# dummy_battery.net
KiCad netlist of a schematic drawn in EAGLE
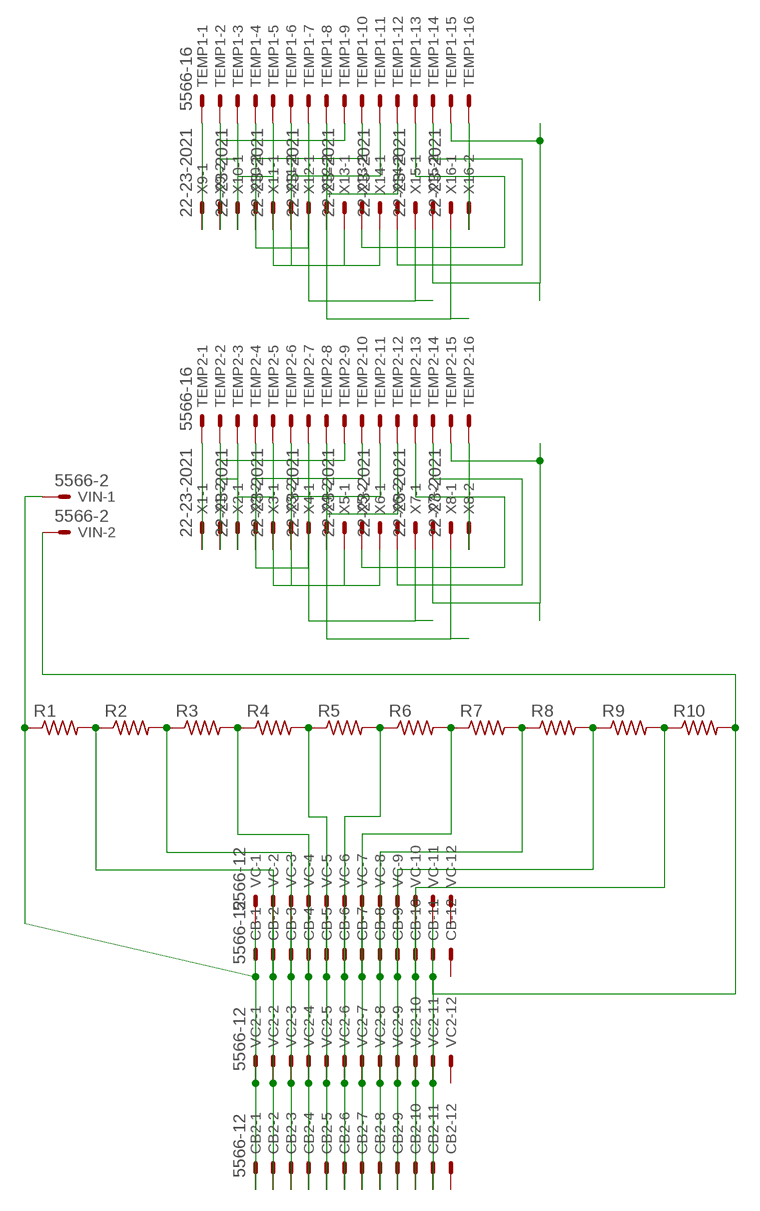
[diagram p0: schematic, sheet 1]

(export (version "E")
  (design (tool "Eeschema 10.0.6"))
  (components
    (comp (ref "CB")
      (value "5566-12")
      (footprint "eagle-import:5566-12")
      (fields (field (name "MF") "MOLEX"))
      (libsource (lib "eagle-import") (part "5566-12"))
    )
    (comp (ref "CB2")
      (value "5566-12")
      (footprint "eagle-import:5566-12")
      (fields (field (name "MF") "MOLEX"))
      (libsource (lib "eagle-import") (part "5566-12"))
    )
    (comp (ref "R1")
      (value "R-US_R0805")
      (footprint "eagle-import:R0805")
      (libsource (lib "eagle-import") (part "R-US_R0805"))
    )
    (comp (ref "R2")
      (value "R-US_R0805")
      (footprint "eagle-import:R0805")
      (libsource (lib "eagle-import") (part "R-US_R0805"))
    )
    (comp (ref "R3")
      (value "R-US_R0805")
      (footprint "eagle-import:R0805")
      (libsource (lib "eagle-import") (part "R-US_R0805"))
    )
    (comp (ref "R4")
      (value "R-US_R0805")
      (footprint "eagle-import:R0805")
      (libsource (lib "eagle-import") (part "R-US_R0805"))
    )
    (comp (ref "R5")
      (value "R-US_R0805")
      (footprint "eagle-import:R0805")
      (libsource (lib "eagle-import") (part "R-US_R0805"))
    )
    (comp (ref "R6")
      (value "R-US_R0805")
      (footprint "eagle-import:R0805")
      (libsource (lib "eagle-import") (part "R-US_R0805"))
    )
    (comp (ref "R7")
      (value "R-US_R0805")
      (footprint "eagle-import:R0805")
      (libsource (lib "eagle-import") (part "R-US_R0805"))
    )
    (comp (ref "R8")
      (value "R-US_R0805")
      (footprint "eagle-import:R0805")
      (libsource (lib "eagle-import") (part "R-US_R0805"))
    )
    (comp (ref "R9")
      (value "R-US_R0805")
      (footprint "eagle-import:R0805")
      (libsource (lib "eagle-import") (part "R-US_R0805"))
    )
    (comp (ref "R10")
      (value "R-US_R0805")
      (footprint "eagle-import:R0805")
      (libsource (lib "eagle-import") (part "R-US_R0805"))
    )
    (comp (ref "TEMP1")
      (value "5566-16")
      (footprint "eagle-import:5566-16")
      (fields (field (name "MF") "MOLEX"))
      (libsource (lib "eagle-import") (part "5566-16"))
    )
    (comp (ref "TEMP2")
      (value "5566-16")
      (footprint "eagle-import:5566-16")
      (fields (field (name "MF") "MOLEX"))
      (libsource (lib "eagle-import") (part "5566-16"))
    )
    (comp (ref "VC")
      (value "5566-12")
      (footprint "eagle-import:5566-12")
      (fields (field (name "MF") "MOLEX"))
      (libsource (lib "eagle-import") (part "5566-12"))
    )
    (comp (ref "VC2")
      (value "5566-12")
      (footprint "eagle-import:5566-12")
      (fields (field (name "MF") "MOLEX"))
      (libsource (lib "eagle-import") (part "5566-12"))
    )
    (comp (ref "VIN")
      (value "5566-2")
      (footprint "eagle-import:5566-2")
      (fields (field (name "MF") "MOLEX"))
      (libsource (lib "eagle-import") (part "5566-2"))
    )
    (comp (ref "X1")
      (value "22-23-2021")
      (footprint "eagle-import:22-23-2021")
      (fields (field (name "MF") "MOLEX"))
      (libsource (lib "eagle-import") (part "22-23-2021"))
    )
    (comp (ref "X2")
      (value "22-23-2021")
      (footprint "eagle-import:22-23-2021")
      (fields (field (name "MF") "MOLEX"))
      (libsource (lib "eagle-import") (part "22-23-2021"))
    )
    (comp (ref "X3")
      (value "22-23-2021")
      (footprint "eagle-import:22-23-2021")
      (fields (field (name "MF") "MOLEX"))
      (libsource (lib "eagle-import") (part "22-23-2021"))
    )
    (comp (ref "X4")
      (value "22-23-2021")
      (footprint "eagle-import:22-23-2021")
      (fields (field (name "MF") "MOLEX"))
      (libsource (lib "eagle-import") (part "22-23-2021"))
    )
    (comp (ref "X5")
      (value "22-23-2021")
      (footprint "eagle-import:22-23-2021")
      (fields (field (name "MF") "MOLEX"))
      (libsource (lib "eagle-import") (part "22-23-2021"))
    )
    (comp (ref "X6")
      (value "22-23-2021")
      (footprint "eagle-import:22-23-2021")
      (fields (field (name "MF") "MOLEX"))
      (libsource (lib "eagle-import") (part "22-23-2021"))
    )
    (comp (ref "X7")
      (value "22-23-2021")
      (footprint "eagle-import:22-23-2021")
      (fields (field (name "MF") "MOLEX"))
      (libsource (lib "eagle-import") (part "22-23-2021"))
    )
    (comp (ref "X8")
      (value "22-23-2021")
      (footprint "eagle-import:22-23-2021")
      (fields (field (name "MF") "MOLEX"))
      (libsource (lib "eagle-import") (part "22-23-2021"))
    )
    (comp (ref "X9")
      (value "22-23-2021")
      (footprint "eagle-import:22-23-2021")
      (fields (field (name "MF") "MOLEX"))
      (libsource (lib "eagle-import") (part "22-23-2021"))
    )
    (comp (ref "X10")
      (value "22-23-2021")
      (footprint "eagle-import:22-23-2021")
      (fields (field (name "MF") "MOLEX"))
      (libsource (lib "eagle-import") (part "22-23-2021"))
    )
    (comp (ref "X11")
      (value "22-23-2021")
      (footprint "eagle-import:22-23-2021")
      (fields (field (name "MF") "MOLEX"))
      (libsource (lib "eagle-import") (part "22-23-2021"))
    )
    (comp (ref "X12")
      (value "22-23-2021")
      (footprint "eagle-import:22-23-2021")
      (fields (field (name "MF") "MOLEX"))
      (libsource (lib "eagle-import") (part "22-23-2021"))
    )
    (comp (ref "X13")
      (value "22-23-2021")
      (footprint "eagle-import:22-23-2021")
      (fields (field (name "MF") "MOLEX"))
      (libsource (lib "eagle-import") (part "22-23-2021"))
    )
    (comp (ref "X14")
      (value "22-23-2021")
      (footprint "eagle-import:22-23-2021")
      (fields (field (name "MF") "MOLEX"))
      (libsource (lib "eagle-import") (part "22-23-2021"))
    )
    (comp (ref "X15")
      (value "22-23-2021")
      (footprint "eagle-import:22-23-2021")
      (fields (field (name "MF") "MOLEX"))
      (libsource (lib "eagle-import") (part "22-23-2021"))
    )
    (comp (ref "X16")
      (value "22-23-2021")
      (footprint "eagle-import:22-23-2021")
      (fields (field (name "MF") "MOLEX"))
      (libsource (lib "eagle-import") (part "22-23-2021"))
    )
  )
  (nets
    (net (code "1") (name "Net-(CB2A-S)") (class "Default")
      (node (ref "CB") (pin "1") (pinfunction "S_1") (pintype "passive"))
      (node (ref "CB2") (pin "1") (pinfunction "S_1") (pintype "passive"))
      (node (ref "R1") (pin "1") (pinfunction "1_1") (pintype "passive"))
      (node (ref "VC") (pin "1") (pinfunction "S_1") (pintype "passive"))
      (node (ref "VC2") (pin "1") (pinfunction "S_1") (pintype "passive"))
      (node (ref "VIN") (pin "1") (pinfunction "S_1") (pintype "passive"))
    )
    (net (code "2") (name "Net-(CB2B-S)") (class "Default")
      (node (ref "CB") (pin "10") (pinfunction "S_10") (pintype "passive"))
      (node (ref "CB2") (pin "10") (pinfunction "S_10") (pintype "passive"))
      (node (ref "R10") (pin "1") (pinfunction "1_1") (pintype "passive"))
      (node (ref "R9") (pin "2") (pinfunction "2_2") (pintype "passive"))
      (node (ref "VC") (pin "10") (pinfunction "S_10") (pintype "passive"))
      (node (ref "VC2") (pin "10") (pinfunction "S_10") (pintype "passive"))
    )
    (net (code "3") (name "Net-(CB2C-S)") (class "Default")
      (node (ref "CB") (pin "11") (pinfunction "S_11") (pintype "passive"))
      (node (ref "CB2") (pin "11") (pinfunction "S_11") (pintype "passive"))
      (node (ref "R10") (pin "2") (pinfunction "2_2") (pintype "passive"))
      (node (ref "VC") (pin "11") (pinfunction "S_11") (pintype "passive"))
      (node (ref "VC2") (pin "11") (pinfunction "S_11") (pintype "passive"))
      (node (ref "VIN") (pin "2") (pinfunction "S_2") (pintype "passive"))
    )
    (net (code "4") (name "Net-(CB2E-S)") (class "Default")
      (node (ref "CB") (pin "2") (pinfunction "S_2") (pintype "passive"))
      (node (ref "CB2") (pin "2") (pinfunction "S_2") (pintype "passive"))
      (node (ref "R1") (pin "2") (pinfunction "2_2") (pintype "passive"))
      (node (ref "R2") (pin "1") (pinfunction "1_1") (pintype "passive"))
      (node (ref "VC") (pin "2") (pinfunction "S_2") (pintype "passive"))
      (node (ref "VC2") (pin "2") (pinfunction "S_2") (pintype "passive"))
    )
    (net (code "5") (name "Net-(CB2F-S)") (class "Default")
      (node (ref "CB") (pin "3") (pinfunction "S_3") (pintype "passive"))
      (node (ref "CB2") (pin "3") (pinfunction "S_3") (pintype "passive"))
      (node (ref "R2") (pin "2") (pinfunction "2_2") (pintype "passive"))
      (node (ref "R3") (pin "1") (pinfunction "1_1") (pintype "passive"))
      (node (ref "VC") (pin "3") (pinfunction "S_3") (pintype "passive"))
      (node (ref "VC2") (pin "3") (pinfunction "S_3") (pintype "passive"))
    )
    (net (code "6") (name "Net-(CB2G-S)") (class "Default")
      (node (ref "CB") (pin "4") (pinfunction "S_4") (pintype "passive"))
      (node (ref "CB2") (pin "4") (pinfunction "S_4") (pintype "passive"))
      (node (ref "R3") (pin "2") (pinfunction "2_2") (pintype "passive"))
      (node (ref "R4") (pin "1") (pinfunction "1_1") (pintype "passive"))
      (node (ref "VC") (pin "4") (pinfunction "S_4") (pintype "passive"))
      (node (ref "VC2") (pin "4") (pinfunction "S_4") (pintype "passive"))
    )
    (net (code "7") (name "Net-(CB2H-S)") (class "Default")
      (node (ref "CB") (pin "5") (pinfunction "S_5") (pintype "passive"))
      (node (ref "CB2") (pin "5") (pinfunction "S_5") (pintype "passive"))
      (node (ref "R4") (pin "2") (pinfunction "2_2") (pintype "passive"))
      (node (ref "R5") (pin "1") (pinfunction "1_1") (pintype "passive"))
      (node (ref "VC") (pin "5") (pinfunction "S_5") (pintype "passive"))
      (node (ref "VC2") (pin "5") (pinfunction "S_5") (pintype "passive"))
    )
    (net (code "8") (name "Net-(CB2I-S)") (class "Default")
      (node (ref "CB") (pin "6") (pinfunction "S_6") (pintype "passive"))
      (node (ref "CB2") (pin "6") (pinfunction "S_6") (pintype "passive"))
      (node (ref "R5") (pin "2") (pinfunction "2_2") (pintype "passive"))
      (node (ref "R6") (pin "1") (pinfunction "1_1") (pintype "passive"))
      (node (ref "VC") (pin "6") (pinfunction "S_6") (pintype "passive"))
      (node (ref "VC2") (pin "6") (pinfunction "S_6") (pintype "passive"))
    )
    (net (code "9") (name "Net-(CB2J-S)") (class "Default")
      (node (ref "CB") (pin "7") (pinfunction "S_7") (pintype "passive"))
      (node (ref "CB2") (pin "7") (pinfunction "S_7") (pintype "passive"))
      (node (ref "R6") (pin "2") (pinfunction "2_2") (pintype "passive"))
      (node (ref "R7") (pin "1") (pinfunction "1_1") (pintype "passive"))
      (node (ref "VC") (pin "7") (pinfunction "S_7") (pintype "passive"))
      (node (ref "VC2") (pin "7") (pinfunction "S_7") (pintype "passive"))
    )
    (net (code "10") (name "Net-(CB2K-S)") (class "Default")
      (node (ref "CB") (pin "8") (pinfunction "S_8") (pintype "passive"))
      (node (ref "CB2") (pin "8") (pinfunction "S_8") (pintype "passive"))
      (node (ref "R7") (pin "2") (pinfunction "2_2") (pintype "passive"))
      (node (ref "R8") (pin "1") (pinfunction "1_1") (pintype "passive"))
      (node (ref "VC") (pin "8") (pinfunction "S_8") (pintype "passive"))
      (node (ref "VC2") (pin "8") (pinfunction "S_8") (pintype "passive"))
    )
    (net (code "11") (name "Net-(CB2L-S)") (class "Default")
      (node (ref "CB") (pin "9") (pinfunction "S_9") (pintype "passive"))
      (node (ref "CB2") (pin "9") (pinfunction "S_9") (pintype "passive"))
      (node (ref "R8") (pin "2") (pinfunction "2_2") (pintype "passive"))
      (node (ref "R9") (pin "1") (pinfunction "1_1") (pintype "passive"))
      (node (ref "VC") (pin "9") (pinfunction "S_9") (pintype "passive"))
      (node (ref "VC2") (pin "9") (pinfunction "S_9") (pintype "passive"))
    )
    (net (code "12") (name "Net-(TEMP1A-S)") (class "Default")
      (node (ref "TEMP1") (pin "1") (pinfunction "S_1") (pintype "passive"))
      (node (ref "X9") (pin "1") (pinfunction "S_1") (pintype "passive"))
    )
    (net (code "13") (name "Net-(TEMP1B-S)") (class "Default")
      (node (ref "TEMP1") (pin "10") (pinfunction "S_10") (pintype "passive"))
      (node (ref "X10") (pin "2") (pinfunction "S_2") (pintype "passive"))
    )
    (net (code "14") (name "Net-(TEMP1C-S)") (class "Default")
      (node (ref "TEMP1") (pin "11") (pinfunction "S_11") (pintype "passive"))
      (node (ref "X11") (pin "2") (pinfunction "S_2") (pintype "passive"))
    )
    (net (code "15") (name "Net-(TEMP1D-S)") (class "Default")
      (node (ref "TEMP1") (pin "12") (pinfunction "S_12") (pintype "passive"))
      (node (ref "X12") (pin "2") (pinfunction "S_2") (pintype "passive"))
    )
    (net (code "16") (name "Net-(TEMP1E-S)") (class "Default")
      (node (ref "TEMP1") (pin "13") (pinfunction "S_13") (pintype "passive"))
      (node (ref "X13") (pin "2") (pinfunction "S_2") (pintype "passive"))
    )
    (net (code "17") (name "Net-(TEMP1F-S)") (class "Default")
      (node (ref "TEMP1") (pin "14") (pinfunction "S_14") (pintype "passive"))
      (node (ref "X14") (pin "2") (pinfunction "S_2") (pintype "passive"))
    )
    (net (code "18") (name "Net-(TEMP1G-S)") (class "Default")
      (node (ref "TEMP1") (pin "15") (pinfunction "S_15") (pintype "passive"))
      (node (ref "X15") (pin "2") (pinfunction "S_2") (pintype "passive"))
    )
    (net (code "19") (name "Net-(TEMP1H-S)") (class "Default")
      (node (ref "TEMP1") (pin "16") (pinfunction "S_16") (pintype "passive"))
      (node (ref "X16") (pin "2") (pinfunction "S_2") (pintype "passive"))
    )
    (net (code "20") (name "Net-(TEMP1I-S)") (class "Default")
      (node (ref "TEMP1") (pin "2") (pinfunction "S_2") (pintype "passive"))
      (node (ref "X10") (pin "1") (pinfunction "S_1") (pintype "passive"))
    )
    (net (code "21") (name "Net-(TEMP1J-S)") (class "Default")
      (node (ref "TEMP1") (pin "3") (pinfunction "S_3") (pintype "passive"))
      (node (ref "X11") (pin "1") (pinfunction "S_1") (pintype "passive"))
    )
    (net (code "22") (name "Net-(TEMP1K-S)") (class "Default")
      (node (ref "TEMP1") (pin "4") (pinfunction "S_4") (pintype "passive"))
      (node (ref "X12") (pin "1") (pinfunction "S_1") (pintype "passive"))
    )
    (net (code "23") (name "Net-(TEMP1L-S)") (class "Default")
      (node (ref "TEMP1") (pin "5") (pinfunction "S_5") (pintype "passive"))
      (node (ref "X13") (pin "1") (pinfunction "S_1") (pintype "passive"))
    )
    (net (code "24") (name "Net-(TEMP1M-S)") (class "Default")
      (node (ref "TEMP1") (pin "6") (pinfunction "S_6") (pintype "passive"))
      (node (ref "X14") (pin "1") (pinfunction "S_1") (pintype "passive"))
    )
    (net (code "25") (name "Net-(TEMP1N-S)") (class "Default")
      (node (ref "TEMP1") (pin "7") (pinfunction "S_7") (pintype "passive"))
      (node (ref "X15") (pin "1") (pinfunction "S_1") (pintype "passive"))
    )
    (net (code "26") (name "Net-(TEMP1O-S)") (class "Default")
      (node (ref "TEMP1") (pin "8") (pinfunction "S_8") (pintype "passive"))
      (node (ref "X16") (pin "1") (pinfunction "S_1") (pintype "passive"))
    )
    (net (code "27") (name "Net-(TEMP1P-S)") (class "Default")
      (node (ref "TEMP1") (pin "9") (pinfunction "S_9") (pintype "passive"))
      (node (ref "X9") (pin "2") (pinfunction "S_2") (pintype "passive"))
    )
    (net (code "28") (name "Net-(TEMP2A-S)") (class "Default")
      (node (ref "TEMP2") (pin "1") (pinfunction "S_1") (pintype "passive"))
      (node (ref "X1") (pin "1") (pinfunction "S_1") (pintype "passive"))
    )
    (net (code "29") (name "Net-(TEMP2B-S)") (class "Default")
      (node (ref "TEMP2") (pin "10") (pinfunction "S_10") (pintype "passive"))
      (node (ref "X2") (pin "2") (pinfunction "S_2") (pintype "passive"))
    )
    (net (code "30") (name "Net-(TEMP2C-S)") (class "Default")
      (node (ref "TEMP2") (pin "11") (pinfunction "S_11") (pintype "passive"))
      (node (ref "X3") (pin "2") (pinfunction "S_2") (pintype "passive"))
    )
    (net (code "31") (name "Net-(TEMP2D-S)") (class "Default")
      (node (ref "TEMP2") (pin "12") (pinfunction "S_12") (pintype "passive"))
      (node (ref "X4") (pin "2") (pinfunction "S_2") (pintype "passive"))
    )
    (net (code "32") (name "Net-(TEMP2E-S)") (class "Default")
      (node (ref "TEMP2") (pin "13") (pinfunction "S_13") (pintype "passive"))
      (node (ref "X5") (pin "2") (pinfunction "S_2") (pintype "passive"))
    )
    (net (code "33") (name "Net-(TEMP2F-S)") (class "Default")
      (node (ref "TEMP2") (pin "14") (pinfunction "S_14") (pintype "passive"))
      (node (ref "X6") (pin "2") (pinfunction "S_2") (pintype "passive"))
    )
    (net (code "34") (name "Net-(TEMP2G-S)") (class "Default")
      (node (ref "TEMP2") (pin "15") (pinfunction "S_15") (pintype "passive"))
      (node (ref "X7") (pin "2") (pinfunction "S_2") (pintype "passive"))
    )
    (net (code "35") (name "Net-(TEMP2H-S)") (class "Default")
      (node (ref "TEMP2") (pin "16") (pinfunction "S_16") (pintype "passive"))
      (node (ref "X8") (pin "2") (pinfunction "S_2") (pintype "passive"))
    )
    (net (code "36") (name "Net-(TEMP2I-S)") (class "Default")
      (node (ref "TEMP2") (pin "2") (pinfunction "S_2") (pintype "passive"))
      (node (ref "X2") (pin "1") (pinfunction "S_1") (pintype "passive"))
    )
    (net (code "37") (name "Net-(TEMP2J-S)") (class "Default")
      (node (ref "TEMP2") (pin "3") (pinfunction "S_3") (pintype "passive"))
      (node (ref "X3") (pin "1") (pinfunction "S_1") (pintype "passive"))
    )
    (net (code "38") (name "Net-(TEMP2K-S)") (class "Default")
      (node (ref "TEMP2") (pin "4") (pinfunction "S_4") (pintype "passive"))
      (node (ref "X4") (pin "1") (pinfunction "S_1") (pintype "passive"))
    )
    (net (code "39") (name "Net-(TEMP2L-S)") (class "Default")
      (node (ref "TEMP2") (pin "5") (pinfunction "S_5") (pintype "passive"))
      (node (ref "X5") (pin "1") (pinfunction "S_1") (pintype "passive"))
    )
    (net (code "40") (name "Net-(TEMP2M-S)") (class "Default")
      (node (ref "TEMP2") (pin "6") (pinfunction "S_6") (pintype "passive"))
      (node (ref "X6") (pin "1") (pinfunction "S_1") (pintype "passive"))
    )
    (net (code "41") (name "Net-(TEMP2N-S)") (class "Default")
      (node (ref "TEMP2") (pin "7") (pinfunction "S_7") (pintype "passive"))
      (node (ref "X7") (pin "1") (pinfunction "S_1") (pintype "passive"))
    )
    (net (code "42") (name "Net-(TEMP2O-S)") (class "Default")
      (node (ref "TEMP2") (pin "8") (pinfunction "S_8") (pintype "passive"))
      (node (ref "X8") (pin "1") (pinfunction "S_1") (pintype "passive"))
    )
    (net (code "43") (name "Net-(TEMP2P-S)") (class "Default")
      (node (ref "TEMP2") (pin "9") (pinfunction "S_9") (pintype "passive"))
      (node (ref "X1") (pin "2") (pinfunction "S_2") (pintype "passive"))
    )
    (net (code "44") (name "unconnected-(CB2D-S-Pad12)") (class "Default")
      (node (ref "CB2") (pin "12") (pinfunction "S_12") (pintype "passive"))
    )
    (net (code "45") (name "unconnected-(CBD-S-Pad12)") (class "Default")
      (node (ref "CB") (pin "12") (pinfunction "S_12") (pintype "passive"))
    )
    (net (code "46") (name "unconnected-(VC2D-S-Pad12)") (class "Default")
      (node (ref "VC2") (pin "12") (pinfunction "S_12") (pintype "passive"))
    )
    (net (code "47") (name "unconnected-(VCD-S-Pad12)") (class "Default")
      (node (ref "VC") (pin "12") (pinfunction "S_12") (pintype "passive"))
    )
  )
)
